# touch-switch-controller.net
KiCad netlist of a schematic drawn in EAGLE
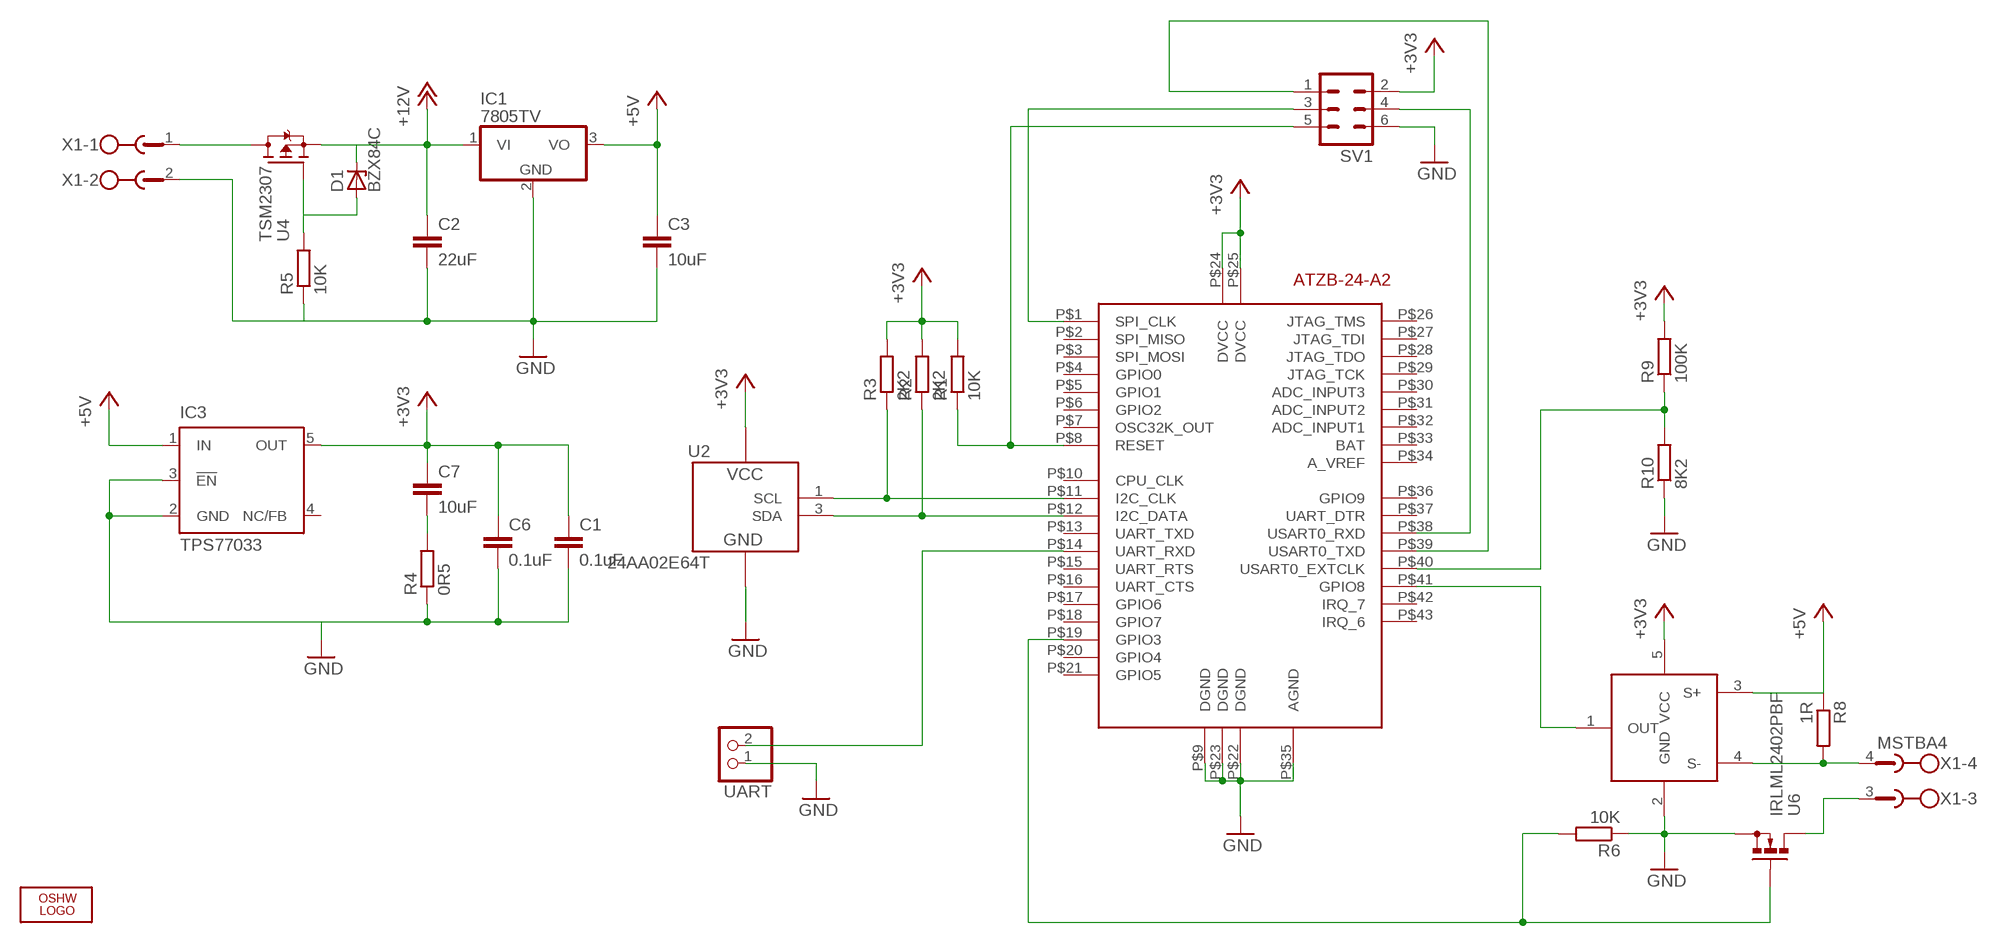
[diagram p0: schematic, sheet 1]

(export (version "E")
  (design (tool "Eeschema 10.0.6"))
  (components
    (comp (ref "C1")
      (value "0.1uF")
      (footprint "eagle-import:C0603")
      (libsource (lib "eagle-import") (part "C-EUC0603"))
    )
    (comp (ref "C2")
      (value "22uF")
      (footprint "eagle-import:C1210")
      (libsource (lib "eagle-import") (part "C-EUC1210"))
    )
    (comp (ref "C3")
      (value "10uF")
      (footprint "eagle-import:C1210")
      (libsource (lib "eagle-import") (part "C-EUC1210"))
    )
    (comp (ref "C6")
      (value "0.1uF")
      (footprint "eagle-import:C0603")
      (libsource (lib "eagle-import") (part "C-EUC0603"))
    )
    (comp (ref "C7")
      (value "10uF")
      (footprint "eagle-import:C1210")
      (libsource (lib "eagle-import") (part "C-EUC1210"))
    )
    (comp (ref "D1")
      (value "BZX84C")
      (footprint "eagle-import:SOT23")
      (libsource (lib "eagle-import") (part "BZX84C"))
    )
    (comp (ref "IC1")
      (value "7805TV")
      (footprint "eagle-import:TO220V")
      (libsource (lib "eagle-import") (part "78TV05"))
    )
    (comp (ref "IC3")
      (value "TPS77033")
      (footprint "eagle-import:SOT23-DBV")
      (fields (field (name "MF") "TEXAS INSTRUMENTS") (field (name "MPN") "TPS77033DBVT"))
      (libsource (lib "eagle-import") (part "TPS77033"))
    )
    (comp (ref "LOGO1")
      (value "OSHW_LOGO_FILLX0100-NT")
      (footprint "eagle-import:OSHW_FILLX100_NOTEXT")
      (libsource (lib "eagle-import") (part "OSHW_LOGO_FILLX0100-NT"))
    )
    (comp (ref "R1")
      (value "10K")
      (footprint "eagle-import:R0603")
      (libsource (lib "eagle-import") (part "R-EU_R0603"))
    )
    (comp (ref "R2")
      (value "2K2")
      (footprint "eagle-import:R0603")
      (libsource (lib "eagle-import") (part "R-EU_R0603"))
    )
    (comp (ref "R3")
      (value "2K2")
      (footprint "eagle-import:R0603")
      (libsource (lib "eagle-import") (part "R-EU_R0603"))
    )
    (comp (ref "R4")
      (value "0R5")
      (footprint "eagle-import:R0603")
      (libsource (lib "eagle-import") (part "R-EU_R0603"))
    )
    (comp (ref "R5")
      (value "10K")
      (footprint "eagle-import:R0603")
      (libsource (lib "eagle-import") (part "R-EU_R0603"))
    )
    (comp (ref "R6")
      (value "10K")
      (footprint "eagle-import:R0603")
      (libsource (lib "eagle-import") (part "R-EU_R0603"))
    )
    (comp (ref "R8")
      (value "1R")
      (footprint "eagle-import:R0603")
      (libsource (lib "eagle-import") (part "R-EU_R0603"))
    )
    (comp (ref "R9")
      (value "100K")
      (footprint "eagle-import:R0603")
      (libsource (lib "eagle-import") (part "R-EU_R0603"))
    )
    (comp (ref "R10")
      (value "8K2")
      (footprint "eagle-import:R0603")
      (libsource (lib "eagle-import") (part "R-EU_R0603"))
    )
    (comp (ref "SV1")
      (value "MA03-2")
      (footprint "eagle-import:MA03-2")
      (libsource (lib "eagle-import") (part "MA03-2"))
    )
    (comp (ref "U$3")
      (value "ATZB-24-A2")
      (footprint "eagle-import:ATZB-24-A2")
      (libsource (lib "eagle-import") (part "ATZB-24-A2"))
    )
    (comp (ref "U1")
      (value "ZXCT1086")
      (footprint "eagle-import:SOT23-5L")
      (libsource (lib "eagle-import") (part "ZXCT1086"))
    )
    (comp (ref "U2")
      (value "24AA02E64T")
      (footprint "eagle-import:SOT23-5L")
      (libsource (lib "eagle-import") (part "24AA02E64T"))
    )
    (comp (ref "U4")
      (value "TSM2307")
      (footprint "eagle-import:SOT23")
      (libsource (lib "eagle-import") (part "TSM2307"))
    )
    (comp (ref "U6")
      (value "IRLML2402PBF")
      (footprint "eagle-import:SOT23")
      (libsource (lib "eagle-import") (part "MMBF170"))
    )
    (comp (ref "UART")
      (value "PINHD-1X2")
      (footprint "eagle-import:1X02")
      (libsource (lib "eagle-import") (part "PINHD-1X2"))
    )
    (comp (ref "X1")
      (value "MSTBA4")
      (footprint "eagle-import:MSTBA4")
      (fields (field (name "MF") "FARNELL") (field (name "MPN") "1757268"))
      (libsource (lib "eagle-import") (part "MSTBA4"))
    )
  )
  (nets
    (net (code "1") (name "+3V3") (class "Default")
      (node (ref "C1") (pin "1") (pinfunction "1_1") (pintype "passive"))
      (node (ref "C6") (pin "1") (pinfunction "1_1") (pintype "passive"))
      (node (ref "C7") (pin "1") (pinfunction "1_1") (pintype "passive"))
      (node (ref "IC3") (pin "5") (pinfunction "OUT_5") (pintype "passive"))
      (node (ref "R1") (pin "2") (pinfunction "2_2") (pintype "passive"))
      (node (ref "R2") (pin "2") (pinfunction "2_2") (pintype "passive"))
      (node (ref "R3") (pin "2") (pinfunction "2_2") (pintype "passive"))
      (node (ref "R9") (pin "2") (pinfunction "2_2") (pintype "passive"))
      (node (ref "SV1") (pin "2") (pinfunction "2_2") (pintype "passive"))
      (node (ref "U$3") (pin "P$24") (pinfunction "DVCC_P$24") (pintype "bidirectional"))
      (node (ref "U$3") (pin "P$25") (pinfunction "DVCC_P$25") (pintype "bidirectional"))
      (node (ref "U1") (pin "5") (pinfunction "VCC_5") (pintype "bidirectional"))
      (node (ref "U2") (pin "4") (pinfunction "VCC_4") (pintype "bidirectional"))
    )
    (net (code "2") (name "+5V") (class "Default")
      (node (ref "C3") (pin "1") (pinfunction "1_1") (pintype "passive"))
      (node (ref "IC1") (pin "3") (pinfunction "VO_3") (pintype "passive"))
      (node (ref "IC3") (pin "1") (pinfunction "IN_1") (pintype "input"))
      (node (ref "R8") (pin "1") (pinfunction "1_1") (pintype "passive"))
      (node (ref "U1") (pin "3") (pinfunction "S+_3") (pintype "bidirectional"))
    )
    (net (code "3") (name "+12V") (class "Default")
      (node (ref "C2") (pin "1") (pinfunction "1_1") (pintype "passive"))
      (node (ref "D1") (pin "3") (pinfunction "C_3") (pintype "passive"))
      (node (ref "IC1") (pin "1") (pinfunction "VI_1") (pintype "input"))
      (node (ref "U4") (pin "2") (pinfunction "S_2") (pintype "passive"))
    )
    (net (code "4") (name "GND") (class "Default")
      (node (ref "C1") (pin "2") (pinfunction "2_2") (pintype "passive"))
      (node (ref "C2") (pin "2") (pinfunction "2_2") (pintype "passive"))
      (node (ref "C3") (pin "2") (pinfunction "2_2") (pintype "passive"))
      (node (ref "C6") (pin "2") (pinfunction "2_2") (pintype "passive"))
      (node (ref "IC1") (pin "2") (pinfunction "GND_2") (pintype "passive"))
      (node (ref "IC3") (pin "2") (pinfunction "GND_2") (pintype "power_in"))
      (node (ref "IC3") (pin "3") (pinfunction "~{EN}_3") (pintype "input"))
      (node (ref "R10") (pin "1") (pinfunction "1_1") (pintype "passive"))
      (node (ref "R4") (pin "1") (pinfunction "1_1") (pintype "passive"))
      (node (ref "R5") (pin "1") (pinfunction "1_1") (pintype "passive"))
      (node (ref "R6") (pin "1") (pinfunction "1_1") (pintype "passive"))
      (node (ref "SV1") (pin "6") (pinfunction "6_6") (pintype "passive"))
      (node (ref "U$3") (pin "P$22") (pinfunction "DGND_P$22") (pintype "bidirectional"))
      (node (ref "U$3") (pin "P$23") (pinfunction "DGND_P$23") (pintype "bidirectional"))
      (node (ref "U$3") (pin "P$35") (pinfunction "AGND_P$35") (pintype "bidirectional"))
      (node (ref "U$3") (pin "P$9") (pinfunction "DGND_P$9") (pintype "bidirectional"))
      (node (ref "U1") (pin "2") (pinfunction "GND_2") (pintype "bidirectional"))
      (node (ref "U2") (pin "2") (pinfunction "VSS_2") (pintype "bidirectional"))
      (node (ref "U6") (pin "2") (pinfunction "S_2") (pintype "passive"))
      (node (ref "UART") (pin "1") (pinfunction "1_1") (pintype "passive"))
      (node (ref "X1") (pin "2") (pinfunction "1_2") (pintype "passive"))
    )
    (net (code "5") (name "Net-(C7-Pad2)") (class "Default")
      (node (ref "C7") (pin "2") (pinfunction "2_2") (pintype "passive"))
      (node (ref "R4") (pin "2") (pinfunction "2_2") (pintype "passive"))
    )
    (net (code "6") (name "Net-(D1-A)") (class "Default")
      (node (ref "D1") (pin "1") (pinfunction "A_1") (pintype "passive"))
      (node (ref "R5") (pin "2") (pinfunction "2_2") (pintype "passive"))
      (node (ref "U4") (pin "1") (pinfunction "G_1") (pintype "passive"))
    )
    (net (code "7") (name "Net-(U$3-GPIO3)") (class "Default")
      (node (ref "R6") (pin "2") (pinfunction "2_2") (pintype "passive"))
      (node (ref "U$3") (pin "P$19") (pinfunction "GPIO3_P$19") (pintype "bidirectional"))
      (node (ref "U6") (pin "1") (pinfunction "G_1") (pintype "passive"))
    )
    (net (code "8") (name "Net-(U$3-GPIO8)") (class "Default")
      (node (ref "U$3") (pin "P$41") (pinfunction "GPIO8_P$41") (pintype "bidirectional"))
      (node (ref "U1") (pin "1") (pinfunction "OUT_1") (pintype "bidirectional"))
    )
    (net (code "9") (name "Net-(U$3-I2C_CLK)") (class "Default")
      (node (ref "R3") (pin "1") (pinfunction "1_1") (pintype "passive"))
      (node (ref "U$3") (pin "P$11") (pinfunction "I2C_CLK_P$11") (pintype "bidirectional"))
      (node (ref "U2") (pin "1") (pinfunction "SCL_1") (pintype "bidirectional"))
    )
    (net (code "10") (name "Net-(U$3-I2C_DATA)") (class "Default")
      (node (ref "R2") (pin "1") (pinfunction "1_1") (pintype "passive"))
      (node (ref "U$3") (pin "P$12") (pinfunction "I2C_DATA_P$12") (pintype "bidirectional"))
      (node (ref "U2") (pin "3") (pinfunction "SDA_3") (pintype "bidirectional"))
    )
    (net (code "11") (name "Net-(U$3-RESET)") (class "Default")
      (node (ref "R1") (pin "1") (pinfunction "1_1") (pintype "passive"))
      (node (ref "SV1") (pin "5") (pinfunction "5_5") (pintype "passive"))
      (node (ref "U$3") (pin "P$8") (pinfunction "RESET_P$8") (pintype "bidirectional"))
    )
    (net (code "12") (name "Net-(U$3-SPI_CLK)") (class "Default")
      (node (ref "SV1") (pin "3") (pinfunction "3_3") (pintype "passive"))
      (node (ref "U$3") (pin "P$1") (pinfunction "SPI_CLK_P$1") (pintype "bidirectional"))
    )
    (net (code "13") (name "Net-(U$3-UART_RXD)") (class "Default")
      (node (ref "U$3") (pin "P$14") (pinfunction "UART_RXD_P$14") (pintype "bidirectional"))
      (node (ref "UART") (pin "2") (pinfunction "2_2") (pintype "passive"))
    )
    (net (code "14") (name "Net-(U$3-USART0_EXTCLK)") (class "Default")
      (node (ref "R10") (pin "2") (pinfunction "2_2") (pintype "passive"))
      (node (ref "R9") (pin "1") (pinfunction "1_1") (pintype "passive"))
      (node (ref "U$3") (pin "P$40") (pinfunction "USART0_EXTCLK_P$40") (pintype "bidirectional"))
    )
    (net (code "15") (name "Net-(U$3-USART0_RXD)") (class "Default")
      (node (ref "SV1") (pin "4") (pinfunction "4_4") (pintype "passive"))
      (node (ref "U$3") (pin "P$38") (pinfunction "USART0_RXD_P$38") (pintype "bidirectional"))
    )
    (net (code "16") (name "Net-(U$3-USART0_TXD)") (class "Default")
      (node (ref "SV1") (pin "1") (pinfunction "1_1") (pintype "passive"))
      (node (ref "U$3") (pin "P$39") (pinfunction "USART0_TXD_P$39") (pintype "bidirectional"))
    )
    (net (code "17") (name "Net-(U1-S-)") (class "Default")
      (node (ref "R8") (pin "2") (pinfunction "2_2") (pintype "passive"))
      (node (ref "U1") (pin "4") (pinfunction "S-_4") (pintype "bidirectional"))
      (node (ref "X1") (pin "4") (pinfunction "1_4") (pintype "passive"))
    )
    (net (code "18") (name "Net-(U4-D)") (class "Default")
      (node (ref "U4") (pin "3") (pinfunction "D_3") (pintype "passive"))
      (node (ref "X1") (pin "1") (pinfunction "1_1") (pintype "passive"))
    )
    (net (code "19") (name "Net-(U6-D)") (class "Default")
      (node (ref "U6") (pin "3") (pinfunction "D_3") (pintype "passive"))
      (node (ref "X1") (pin "3") (pinfunction "1_3") (pintype "passive"))
    )
    (net (code "20") (name "unconnected-(IC3-NC{slash}FB-Pad4)") (class "Default")
      (node (ref "IC3") (pin "4") (pinfunction "NC/FB_4") (pintype "passive"))
    )
    (net (code "21") (name "unconnected-(U$3-ADC_INPUT1-PadP$32)") (class "Default")
      (node (ref "U$3") (pin "P$32") (pinfunction "ADC_INPUT1_P$32") (pintype "bidirectional"))
    )
    (net (code "22") (name "unconnected-(U$3-ADC_INPUT2-PadP$31)") (class "Default")
      (node (ref "U$3") (pin "P$31") (pinfunction "ADC_INPUT2_P$31") (pintype "bidirectional"))
    )
    (net (code "23") (name "unconnected-(U$3-ADC_INPUT3-PadP$30)") (class "Default")
      (node (ref "U$3") (pin "P$30") (pinfunction "ADC_INPUT3_P$30") (pintype "bidirectional"))
    )
    (net (code "24") (name "unconnected-(U$3-A_VREF-PadP$34)") (class "Default")
      (node (ref "U$3") (pin "P$34") (pinfunction "A_VREF_P$34") (pintype "bidirectional"))
    )
    (net (code "25") (name "unconnected-(U$3-BAT-PadP$33)") (class "Default")
      (node (ref "U$3") (pin "P$33") (pinfunction "BAT_P$33") (pintype "bidirectional"))
    )
    (net (code "26") (name "unconnected-(U$3-CPU_CLK-PadP$10)") (class "Default")
      (node (ref "U$3") (pin "P$10") (pinfunction "CPU_CLK_P$10") (pintype "bidirectional"))
    )
    (net (code "27") (name "unconnected-(U$3-GPIO0-PadP$4)") (class "Default")
      (node (ref "U$3") (pin "P$4") (pinfunction "GPIO0_P$4") (pintype "bidirectional"))
    )
    (net (code "28") (name "unconnected-(U$3-GPIO1-PadP$5)") (class "Default")
      (node (ref "U$3") (pin "P$5") (pinfunction "GPIO1_P$5") (pintype "bidirectional"))
    )
    (net (code "29") (name "unconnected-(U$3-GPIO2-PadP$6)") (class "Default")
      (node (ref "U$3") (pin "P$6") (pinfunction "GPIO2_P$6") (pintype "bidirectional"))
    )
    (net (code "30") (name "unconnected-(U$3-GPIO4-PadP$20)") (class "Default")
      (node (ref "U$3") (pin "P$20") (pinfunction "GPIO4_P$20") (pintype "bidirectional"))
    )
    (net (code "31") (name "unconnected-(U$3-GPIO5-PadP$21)") (class "Default")
      (node (ref "U$3") (pin "P$21") (pinfunction "GPIO5_P$21") (pintype "bidirectional"))
    )
    (net (code "32") (name "unconnected-(U$3-GPIO6-PadP$17)") (class "Default")
      (node (ref "U$3") (pin "P$17") (pinfunction "GPIO6_P$17") (pintype "bidirectional"))
    )
    (net (code "33") (name "unconnected-(U$3-GPIO7-PadP$18)") (class "Default")
      (node (ref "U$3") (pin "P$18") (pinfunction "GPIO7_P$18") (pintype "bidirectional"))
    )
    (net (code "34") (name "unconnected-(U$3-GPIO9-PadP$36)") (class "Default")
      (node (ref "U$3") (pin "P$36") (pinfunction "GPIO9_P$36") (pintype "bidirectional"))
    )
    (net (code "35") (name "unconnected-(U$3-IRQ_6-PadP$43)") (class "Default")
      (node (ref "U$3") (pin "P$43") (pinfunction "IRQ_6_P$43") (pintype "bidirectional"))
    )
    (net (code "36") (name "unconnected-(U$3-IRQ_7-PadP$42)") (class "Default")
      (node (ref "U$3") (pin "P$42") (pinfunction "IRQ_7_P$42") (pintype "bidirectional"))
    )
    (net (code "37") (name "unconnected-(U$3-JTAG_TCK-PadP$29)") (class "Default")
      (node (ref "U$3") (pin "P$29") (pinfunction "JTAG_TCK_P$29") (pintype "bidirectional"))
    )
    (net (code "38") (name "unconnected-(U$3-JTAG_TDI-PadP$27)") (class "Default")
      (node (ref "U$3") (pin "P$27") (pinfunction "JTAG_TDI_P$27") (pintype "bidirectional"))
    )
    (net (code "39") (name "unconnected-(U$3-JTAG_TDO-PadP$28)") (class "Default")
      (node (ref "U$3") (pin "P$28") (pinfunction "JTAG_TDO_P$28") (pintype "bidirectional"))
    )
    (net (code "40") (name "unconnected-(U$3-JTAG_TMS-PadP$26)") (class "Default")
      (node (ref "U$3") (pin "P$26") (pinfunction "JTAG_TMS_P$26") (pintype "bidirectional"))
    )
    (net (code "41") (name "unconnected-(U$3-OSC32K_OUT-PadP$7)") (class "Default")
      (node (ref "U$3") (pin "P$7") (pinfunction "OSC32K_OUT_P$7") (pintype "bidirectional"))
    )
    (net (code "42") (name "unconnected-(U$3-SPI_MISO-PadP$2)") (class "Default")
      (node (ref "U$3") (pin "P$2") (pinfunction "SPI_MISO_P$2") (pintype "bidirectional"))
    )
    (net (code "43") (name "unconnected-(U$3-SPI_MOSI-PadP$3)") (class "Default")
      (node (ref "U$3") (pin "P$3") (pinfunction "SPI_MOSI_P$3") (pintype "bidirectional"))
    )
    (net (code "44") (name "unconnected-(U$3-UART_CTS-PadP$16)") (class "Default")
      (node (ref "U$3") (pin "P$16") (pinfunction "UART_CTS_P$16") (pintype "bidirectional"))
    )
    (net (code "45") (name "unconnected-(U$3-UART_DTR-PadP$37)") (class "Default")
      (node (ref "U$3") (pin "P$37") (pinfunction "UART_DTR_P$37") (pintype "bidirectional"))
    )
    (net (code "46") (name "unconnected-(U$3-UART_RTS-PadP$15)") (class "Default")
      (node (ref "U$3") (pin "P$15") (pinfunction "UART_RTS_P$15") (pintype "bidirectional"))
    )
    (net (code "47") (name "unconnected-(U$3-UART_TXD-PadP$13)") (class "Default")
      (node (ref "U$3") (pin "P$13") (pinfunction "UART_TXD_P$13") (pintype "bidirectional"))
    )
  )
)
